# tqfp-80.net
KiCad netlist of a schematic drawn in EAGLE
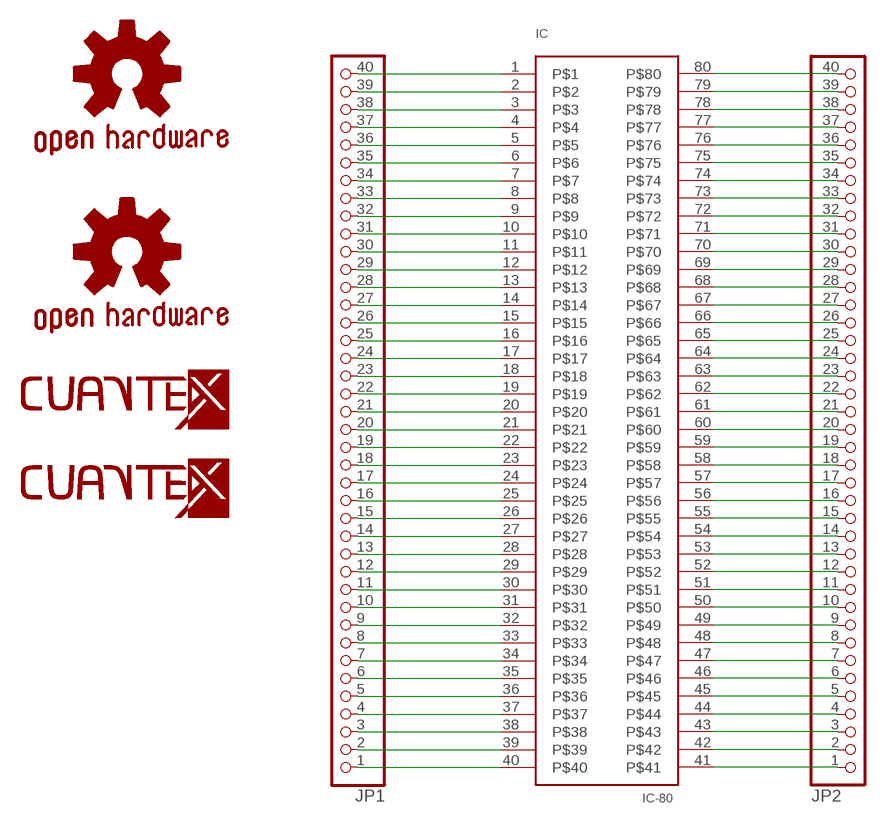
[diagram p0: schematic, sheet 1]

(export (version "E")
  (design (tool "Eeschema 10.0.6"))
  (components
    (comp (ref "GOLD_ORB_SM1")
      (value "OSHWLOGO_GOLD_ORB_SM")
      (footprint "eagle-import:OSHW2")
      (libsource (lib "eagle-import") (part "OSHWLOGO_GOLD_ORB_SM"))
    )
    (comp (ref "GOLD_ORB_SM2")
      (value "OSHWLOGO_GOLD_ORB_SM")
      (footprint "eagle-import:OSHW2")
      (libsource (lib "eagle-import") (part "OSHWLOGO_GOLD_ORB_SM"))
    )
    (comp (ref "IC")
      (value "IC-80")
      (footprint "eagle-import:TQFP-80")
      (libsource (lib "eagle-import") (part "IC-80"))
    )
    (comp (ref "JP1")
      (value "PINHD-1X40")
      (footprint "eagle-import:1X40")
      (libsource (lib "eagle-import") (part "PINHD-1X40"))
    )
    (comp (ref "JP2")
      (value "PINHD-1X40")
      (footprint "eagle-import:1X40")
      (libsource (lib "eagle-import") (part "PINHD-1X40"))
    )
    (comp (ref "U$2")
      (value "LOGO-TOP-30MM")
      (footprint "eagle-import:C-1")
      (libsource (lib "eagle-import") (part "LOGO-TOP-30MM"))
    )
    (comp (ref "U$3")
      (value "LOGO-TOP-15MM")
      (footprint "eagle-import:C-00")
      (libsource (lib "eagle-import") (part "LOGO-TOP-15MM"))
    )
  )
  (nets
    (net (code "1") (name "Net-(IC-P$1)") (class "Default")
      (node (ref "IC") (pin "1") (pinfunction "P$1_1") (pintype "bidirectional"))
      (node (ref "JP1") (pin "40") (pinfunction "40_40") (pintype "passive"))
    )
    (net (code "2") (name "Net-(IC-P$2)") (class "Default")
      (node (ref "IC") (pin "2") (pinfunction "P$2_2") (pintype "bidirectional"))
      (node (ref "JP1") (pin "39") (pinfunction "39_39") (pintype "passive"))
    )
    (net (code "3") (name "Net-(IC-P$3)") (class "Default")
      (node (ref "IC") (pin "3") (pinfunction "P$3_3") (pintype "bidirectional"))
      (node (ref "JP1") (pin "38") (pinfunction "38_38") (pintype "passive"))
    )
    (net (code "4") (name "Net-(IC-P$4)") (class "Default")
      (node (ref "IC") (pin "4") (pinfunction "P$4_4") (pintype "bidirectional"))
      (node (ref "JP1") (pin "37") (pinfunction "37_37") (pintype "passive"))
    )
    (net (code "5") (name "Net-(IC-P$5)") (class "Default")
      (node (ref "IC") (pin "5") (pinfunction "P$5_5") (pintype "bidirectional"))
      (node (ref "JP1") (pin "36") (pinfunction "36_36") (pintype "passive"))
    )
    (net (code "6") (name "Net-(IC-P$6)") (class "Default")
      (node (ref "IC") (pin "6") (pinfunction "P$6_6") (pintype "bidirectional"))
      (node (ref "JP1") (pin "35") (pinfunction "35_35") (pintype "passive"))
    )
    (net (code "7") (name "Net-(IC-P$7)") (class "Default")
      (node (ref "IC") (pin "7") (pinfunction "P$7_7") (pintype "bidirectional"))
      (node (ref "JP1") (pin "34") (pinfunction "34_34") (pintype "passive"))
    )
    (net (code "8") (name "Net-(IC-P$8)") (class "Default")
      (node (ref "IC") (pin "8") (pinfunction "P$8_8") (pintype "bidirectional"))
      (node (ref "JP1") (pin "33") (pinfunction "33_33") (pintype "passive"))
    )
    (net (code "9") (name "Net-(IC-P$9)") (class "Default")
      (node (ref "IC") (pin "9") (pinfunction "P$9_9") (pintype "bidirectional"))
      (node (ref "JP1") (pin "32") (pinfunction "32_32") (pintype "passive"))
    )
    (net (code "10") (name "Net-(IC-P$10)") (class "Default")
      (node (ref "IC") (pin "10") (pinfunction "P$10_10") (pintype "bidirectional"))
      (node (ref "JP1") (pin "31") (pinfunction "31_31") (pintype "passive"))
    )
    (net (code "11") (name "Net-(IC-P$11)") (class "Default")
      (node (ref "IC") (pin "11") (pinfunction "P$11_11") (pintype "bidirectional"))
      (node (ref "JP1") (pin "30") (pinfunction "30_30") (pintype "passive"))
    )
    (net (code "12") (name "Net-(IC-P$12)") (class "Default")
      (node (ref "IC") (pin "12") (pinfunction "P$12_12") (pintype "bidirectional"))
      (node (ref "JP1") (pin "29") (pinfunction "29_29") (pintype "passive"))
    )
    (net (code "13") (name "Net-(IC-P$13)") (class "Default")
      (node (ref "IC") (pin "13") (pinfunction "P$13_13") (pintype "bidirectional"))
      (node (ref "JP1") (pin "28") (pinfunction "28_28") (pintype "passive"))
    )
    (net (code "14") (name "Net-(IC-P$14)") (class "Default")
      (node (ref "IC") (pin "14") (pinfunction "P$14_14") (pintype "bidirectional"))
      (node (ref "JP1") (pin "27") (pinfunction "27_27") (pintype "passive"))
    )
    (net (code "15") (name "Net-(IC-P$15)") (class "Default")
      (node (ref "IC") (pin "15") (pinfunction "P$15_15") (pintype "bidirectional"))
      (node (ref "JP1") (pin "26") (pinfunction "26_26") (pintype "passive"))
    )
    (net (code "16") (name "Net-(IC-P$16)") (class "Default")
      (node (ref "IC") (pin "16") (pinfunction "P$16_16") (pintype "bidirectional"))
      (node (ref "JP1") (pin "25") (pinfunction "25_25") (pintype "passive"))
    )
    (net (code "17") (name "Net-(IC-P$17)") (class "Default")
      (node (ref "IC") (pin "17") (pinfunction "P$17_17") (pintype "bidirectional"))
      (node (ref "JP1") (pin "24") (pinfunction "24_24") (pintype "passive"))
    )
    (net (code "18") (name "Net-(IC-P$18)") (class "Default")
      (node (ref "IC") (pin "18") (pinfunction "P$18_18") (pintype "bidirectional"))
      (node (ref "JP1") (pin "23") (pinfunction "23_23") (pintype "passive"))
    )
    (net (code "19") (name "Net-(IC-P$19)") (class "Default")
      (node (ref "IC") (pin "19") (pinfunction "P$19_19") (pintype "bidirectional"))
      (node (ref "JP1") (pin "22") (pinfunction "22_22") (pintype "passive"))
    )
    (net (code "20") (name "Net-(IC-P$20)") (class "Default")
      (node (ref "IC") (pin "20") (pinfunction "P$20_20") (pintype "bidirectional"))
      (node (ref "JP1") (pin "21") (pinfunction "21_21") (pintype "passive"))
    )
    (net (code "21") (name "Net-(IC-P$21)") (class "Default")
      (node (ref "IC") (pin "21") (pinfunction "P$21_21") (pintype "bidirectional"))
      (node (ref "JP1") (pin "20") (pinfunction "20_20") (pintype "passive"))
    )
    (net (code "22") (name "Net-(IC-P$22)") (class "Default")
      (node (ref "IC") (pin "22") (pinfunction "P$22_22") (pintype "bidirectional"))
      (node (ref "JP1") (pin "19") (pinfunction "19_19") (pintype "passive"))
    )
    (net (code "23") (name "Net-(IC-P$23)") (class "Default")
      (node (ref "IC") (pin "23") (pinfunction "P$23_23") (pintype "bidirectional"))
      (node (ref "JP1") (pin "18") (pinfunction "18_18") (pintype "passive"))
    )
    (net (code "24") (name "Net-(IC-P$24)") (class "Default")
      (node (ref "IC") (pin "24") (pinfunction "P$24_24") (pintype "bidirectional"))
      (node (ref "JP1") (pin "17") (pinfunction "17_17") (pintype "passive"))
    )
    (net (code "25") (name "Net-(IC-P$25)") (class "Default")
      (node (ref "IC") (pin "25") (pinfunction "P$25_25") (pintype "bidirectional"))
      (node (ref "JP1") (pin "16") (pinfunction "16_16") (pintype "passive"))
    )
    (net (code "26") (name "Net-(IC-P$26)") (class "Default")
      (node (ref "IC") (pin "26") (pinfunction "P$26_26") (pintype "bidirectional"))
      (node (ref "JP1") (pin "15") (pinfunction "15_15") (pintype "passive"))
    )
    (net (code "27") (name "Net-(IC-P$27)") (class "Default")
      (node (ref "IC") (pin "27") (pinfunction "P$27_27") (pintype "bidirectional"))
      (node (ref "JP1") (pin "14") (pinfunction "14_14") (pintype "passive"))
    )
    (net (code "28") (name "Net-(IC-P$28)") (class "Default")
      (node (ref "IC") (pin "28") (pinfunction "P$28_28") (pintype "bidirectional"))
      (node (ref "JP1") (pin "13") (pinfunction "13_13") (pintype "passive"))
    )
    (net (code "29") (name "Net-(IC-P$29)") (class "Default")
      (node (ref "IC") (pin "29") (pinfunction "P$29_29") (pintype "bidirectional"))
      (node (ref "JP1") (pin "12") (pinfunction "12_12") (pintype "passive"))
    )
    (net (code "30") (name "Net-(IC-P$30)") (class "Default")
      (node (ref "IC") (pin "30") (pinfunction "P$30_30") (pintype "bidirectional"))
      (node (ref "JP1") (pin "11") (pinfunction "11_11") (pintype "passive"))
    )
    (net (code "31") (name "Net-(IC-P$31)") (class "Default")
      (node (ref "IC") (pin "31") (pinfunction "P$31_31") (pintype "bidirectional"))
      (node (ref "JP1") (pin "10") (pinfunction "10_10") (pintype "passive"))
    )
    (net (code "32") (name "Net-(IC-P$32)") (class "Default")
      (node (ref "IC") (pin "32") (pinfunction "P$32_32") (pintype "bidirectional"))
      (node (ref "JP1") (pin "9") (pinfunction "9_9") (pintype "passive"))
    )
    (net (code "33") (name "Net-(IC-P$33)") (class "Default")
      (node (ref "IC") (pin "33") (pinfunction "P$33_33") (pintype "bidirectional"))
      (node (ref "JP1") (pin "8") (pinfunction "8_8") (pintype "passive"))
    )
    (net (code "34") (name "Net-(IC-P$34)") (class "Default")
      (node (ref "IC") (pin "34") (pinfunction "P$34_34") (pintype "bidirectional"))
      (node (ref "JP1") (pin "7") (pinfunction "7_7") (pintype "passive"))
    )
    (net (code "35") (name "Net-(IC-P$35)") (class "Default")
      (node (ref "IC") (pin "35") (pinfunction "P$35_35") (pintype "bidirectional"))
      (node (ref "JP1") (pin "6") (pinfunction "6_6") (pintype "passive"))
    )
    (net (code "36") (name "Net-(IC-P$36)") (class "Default")
      (node (ref "IC") (pin "36") (pinfunction "P$36_36") (pintype "bidirectional"))
      (node (ref "JP1") (pin "5") (pinfunction "5_5") (pintype "passive"))
    )
    (net (code "37") (name "Net-(IC-P$37)") (class "Default")
      (node (ref "IC") (pin "37") (pinfunction "P$37_37") (pintype "bidirectional"))
      (node (ref "JP1") (pin "4") (pinfunction "4_4") (pintype "passive"))
    )
    (net (code "38") (name "Net-(IC-P$38)") (class "Default")
      (node (ref "IC") (pin "38") (pinfunction "P$38_38") (pintype "bidirectional"))
      (node (ref "JP1") (pin "3") (pinfunction "3_3") (pintype "passive"))
    )
    (net (code "39") (name "Net-(IC-P$39)") (class "Default")
      (node (ref "IC") (pin "39") (pinfunction "P$39_39") (pintype "bidirectional"))
      (node (ref "JP1") (pin "2") (pinfunction "2_2") (pintype "passive"))
    )
    (net (code "40") (name "Net-(IC-P$40)") (class "Default")
      (node (ref "IC") (pin "40") (pinfunction "P$40_40") (pintype "bidirectional"))
      (node (ref "JP1") (pin "1") (pinfunction "1_1") (pintype "passive"))
    )
    (net (code "41") (name "Net-(IC-P$41)") (class "Default")
      (node (ref "IC") (pin "41") (pinfunction "P$41_41") (pintype "bidirectional"))
      (node (ref "JP2") (pin "1") (pinfunction "1_1") (pintype "passive"))
    )
    (net (code "42") (name "Net-(IC-P$42)") (class "Default")
      (node (ref "IC") (pin "42") (pinfunction "P$42_42") (pintype "bidirectional"))
      (node (ref "JP2") (pin "2") (pinfunction "2_2") (pintype "passive"))
    )
    (net (code "43") (name "Net-(IC-P$43)") (class "Default")
      (node (ref "IC") (pin "43") (pinfunction "P$43_43") (pintype "bidirectional"))
      (node (ref "JP2") (pin "3") (pinfunction "3_3") (pintype "passive"))
    )
    (net (code "44") (name "Net-(IC-P$44)") (class "Default")
      (node (ref "IC") (pin "44") (pinfunction "P$44_44") (pintype "bidirectional"))
      (node (ref "JP2") (pin "4") (pinfunction "4_4") (pintype "passive"))
    )
    (net (code "45") (name "Net-(IC-P$45)") (class "Default")
      (node (ref "IC") (pin "45") (pinfunction "P$45_45") (pintype "bidirectional"))
      (node (ref "JP2") (pin "5") (pinfunction "5_5") (pintype "passive"))
    )
    (net (code "46") (name "Net-(IC-P$46)") (class "Default")
      (node (ref "IC") (pin "46") (pinfunction "P$46_46") (pintype "bidirectional"))
      (node (ref "JP2") (pin "6") (pinfunction "6_6") (pintype "passive"))
    )
    (net (code "47") (name "Net-(IC-P$47)") (class "Default")
      (node (ref "IC") (pin "47") (pinfunction "P$47_47") (pintype "bidirectional"))
      (node (ref "JP2") (pin "7") (pinfunction "7_7") (pintype "passive"))
    )
    (net (code "48") (name "Net-(IC-P$48)") (class "Default")
      (node (ref "IC") (pin "48") (pinfunction "P$48_48") (pintype "bidirectional"))
      (node (ref "JP2") (pin "8") (pinfunction "8_8") (pintype "passive"))
    )
    (net (code "49") (name "Net-(IC-P$49)") (class "Default")
      (node (ref "IC") (pin "49") (pinfunction "P$49_49") (pintype "bidirectional"))
      (node (ref "JP2") (pin "9") (pinfunction "9_9") (pintype "passive"))
    )
    (net (code "50") (name "Net-(IC-P$50)") (class "Default")
      (node (ref "IC") (pin "50") (pinfunction "P$50_50") (pintype "bidirectional"))
      (node (ref "JP2") (pin "10") (pinfunction "10_10") (pintype "passive"))
    )
    (net (code "51") (name "Net-(IC-P$51)") (class "Default")
      (node (ref "IC") (pin "51") (pinfunction "P$51_51") (pintype "bidirectional"))
      (node (ref "JP2") (pin "11") (pinfunction "11_11") (pintype "passive"))
    )
    (net (code "52") (name "Net-(IC-P$52)") (class "Default")
      (node (ref "IC") (pin "52") (pinfunction "P$52_52") (pintype "bidirectional"))
      (node (ref "JP2") (pin "12") (pinfunction "12_12") (pintype "passive"))
    )
    (net (code "53") (name "Net-(IC-P$53)") (class "Default")
      (node (ref "IC") (pin "53") (pinfunction "P$53_53") (pintype "bidirectional"))
      (node (ref "JP2") (pin "13") (pinfunction "13_13") (pintype "passive"))
    )
    (net (code "54") (name "Net-(IC-P$54)") (class "Default")
      (node (ref "IC") (pin "54") (pinfunction "P$54_54") (pintype "bidirectional"))
      (node (ref "JP2") (pin "14") (pinfunction "14_14") (pintype "passive"))
    )
    (net (code "55") (name "Net-(IC-P$55)") (class "Default")
      (node (ref "IC") (pin "55") (pinfunction "P$55_55") (pintype "bidirectional"))
      (node (ref "JP2") (pin "15") (pinfunction "15_15") (pintype "passive"))
    )
    (net (code "56") (name "Net-(IC-P$56)") (class "Default")
      (node (ref "IC") (pin "56") (pinfunction "P$56_56") (pintype "bidirectional"))
      (node (ref "JP2") (pin "16") (pinfunction "16_16") (pintype "passive"))
    )
    (net (code "57") (name "Net-(IC-P$57)") (class "Default")
      (node (ref "IC") (pin "57") (pinfunction "P$57_57") (pintype "bidirectional"))
      (node (ref "JP2") (pin "17") (pinfunction "17_17") (pintype "passive"))
    )
    (net (code "58") (name "Net-(IC-P$58)") (class "Default")
      (node (ref "IC") (pin "58") (pinfunction "P$58_58") (pintype "bidirectional"))
      (node (ref "JP2") (pin "18") (pinfunction "18_18") (pintype "passive"))
    )
    (net (code "59") (name "Net-(IC-P$59)") (class "Default")
      (node (ref "IC") (pin "59") (pinfunction "P$59_59") (pintype "bidirectional"))
      (node (ref "JP2") (pin "19") (pinfunction "19_19") (pintype "passive"))
    )
    (net (code "60") (name "Net-(IC-P$60)") (class "Default")
      (node (ref "IC") (pin "60") (pinfunction "P$60_60") (pintype "bidirectional"))
      (node (ref "JP2") (pin "20") (pinfunction "20_20") (pintype "passive"))
    )
    (net (code "61") (name "Net-(IC-P$61)") (class "Default")
      (node (ref "IC") (pin "61") (pinfunction "P$61_61") (pintype "bidirectional"))
      (node (ref "JP2") (pin "21") (pinfunction "21_21") (pintype "passive"))
    )
    (net (code "62") (name "Net-(IC-P$62)") (class "Default")
      (node (ref "IC") (pin "62") (pinfunction "P$62_62") (pintype "bidirectional"))
      (node (ref "JP2") (pin "22") (pinfunction "22_22") (pintype "passive"))
    )
    (net (code "63") (name "Net-(IC-P$63)") (class "Default")
      (node (ref "IC") (pin "63") (pinfunction "P$63_63") (pintype "bidirectional"))
      (node (ref "JP2") (pin "23") (pinfunction "23_23") (pintype "passive"))
    )
    (net (code "64") (name "Net-(IC-P$64)") (class "Default")
      (node (ref "IC") (pin "64") (pinfunction "P$64_64") (pintype "bidirectional"))
      (node (ref "JP2") (pin "24") (pinfunction "24_24") (pintype "passive"))
    )
    (net (code "65") (name "Net-(IC-P$65)") (class "Default")
      (node (ref "IC") (pin "65") (pinfunction "P$65_65") (pintype "bidirectional"))
      (node (ref "JP2") (pin "25") (pinfunction "25_25") (pintype "passive"))
    )
    (net (code "66") (name "Net-(IC-P$66)") (class "Default")
      (node (ref "IC") (pin "66") (pinfunction "P$66_66") (pintype "bidirectional"))
      (node (ref "JP2") (pin "26") (pinfunction "26_26") (pintype "passive"))
    )
    (net (code "67") (name "Net-(IC-P$67)") (class "Default")
      (node (ref "IC") (pin "67") (pinfunction "P$67_67") (pintype "bidirectional"))
      (node (ref "JP2") (pin "27") (pinfunction "27_27") (pintype "passive"))
    )
    (net (code "68") (name "Net-(IC-P$68)") (class "Default")
      (node (ref "IC") (pin "68") (pinfunction "P$68_68") (pintype "bidirectional"))
      (node (ref "JP2") (pin "28") (pinfunction "28_28") (pintype "passive"))
    )
    (net (code "69") (name "Net-(IC-P$69)") (class "Default")
      (node (ref "IC") (pin "69") (pinfunction "P$69_69") (pintype "bidirectional"))
      (node (ref "JP2") (pin "29") (pinfunction "29_29") (pintype "passive"))
    )
    (net (code "70") (name "Net-(IC-P$70)") (class "Default")
      (node (ref "IC") (pin "70") (pinfunction "P$70_70") (pintype "bidirectional"))
      (node (ref "JP2") (pin "30") (pinfunction "30_30") (pintype "passive"))
    )
    (net (code "71") (name "Net-(IC-P$71)") (class "Default")
      (node (ref "IC") (pin "71") (pinfunction "P$71_71") (pintype "bidirectional"))
      (node (ref "JP2") (pin "31") (pinfunction "31_31") (pintype "passive"))
    )
    (net (code "72") (name "Net-(IC-P$72)") (class "Default")
      (node (ref "IC") (pin "72") (pinfunction "P$72_72") (pintype "bidirectional"))
      (node (ref "JP2") (pin "32") (pinfunction "32_32") (pintype "passive"))
    )
    (net (code "73") (name "Net-(IC-P$73)") (class "Default")
      (node (ref "IC") (pin "73") (pinfunction "P$73_73") (pintype "bidirectional"))
      (node (ref "JP2") (pin "33") (pinfunction "33_33") (pintype "passive"))
    )
    (net (code "74") (name "Net-(IC-P$74)") (class "Default")
      (node (ref "IC") (pin "74") (pinfunction "P$74_74") (pintype "bidirectional"))
      (node (ref "JP2") (pin "34") (pinfunction "34_34") (pintype "passive"))
    )
    (net (code "75") (name "Net-(IC-P$75)") (class "Default")
      (node (ref "IC") (pin "75") (pinfunction "P$75_75") (pintype "bidirectional"))
      (node (ref "JP2") (pin "35") (pinfunction "35_35") (pintype "passive"))
    )
    (net (code "76") (name "Net-(IC-P$76)") (class "Default")
      (node (ref "IC") (pin "76") (pinfunction "P$76_76") (pintype "bidirectional"))
      (node (ref "JP2") (pin "36") (pinfunction "36_36") (pintype "passive"))
    )
    (net (code "77") (name "Net-(IC-P$77)") (class "Default")
      (node (ref "IC") (pin "77") (pinfunction "P$77_77") (pintype "bidirectional"))
      (node (ref "JP2") (pin "37") (pinfunction "37_37") (pintype "passive"))
    )
    (net (code "78") (name "Net-(IC-P$78)") (class "Default")
      (node (ref "IC") (pin "78") (pinfunction "P$78_78") (pintype "bidirectional"))
      (node (ref "JP2") (pin "38") (pinfunction "38_38") (pintype "passive"))
    )
    (net (code "79") (name "Net-(IC-P$79)") (class "Default")
      (node (ref "IC") (pin "79") (pinfunction "P$79_79") (pintype "bidirectional"))
      (node (ref "JP2") (pin "39") (pinfunction "39_39") (pintype "passive"))
    )
    (net (code "80") (name "Net-(IC-P$80)") (class "Default")
      (node (ref "IC") (pin "80") (pinfunction "P$80_80") (pintype "bidirectional"))
      (node (ref "JP2") (pin "40") (pinfunction "40_40") (pintype "passive"))
    )
  )
)
